# bat_v.net
KiCad netlist of a schematic drawn in Altium Designer
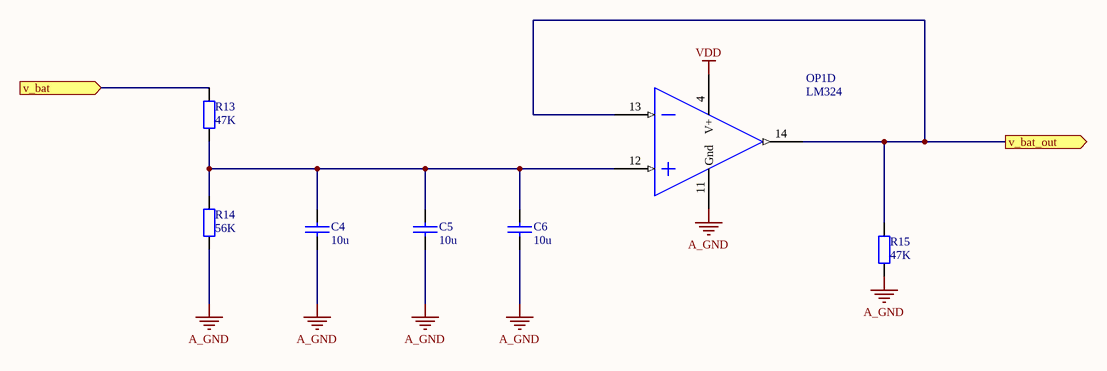
[diagram p0: bat_v.SchDoc]

(export (version "E")
  (design (tool "Eeschema 10.0.6"))
  (components
    (comp (ref "C4") (value "10u") (description "Capacitor") (libsource (lib "EceParts") (part "Cap")))
    (comp (ref "C5") (value "10u") (description "Capacitor") (libsource (lib "EceParts") (part "Cap")))
    (comp (ref "C6") (value "10u") (description "Capacitor") (libsource (lib "EceParts") (part "Cap")))
    (comp (ref "OP1") (value "LM324") (libsource (lib "EceParts") (part "LM324")))
    (comp (ref "R13") (value "47K") (description "Resistor") (libsource (lib "EceParts") (part "Resistor")))
    (comp (ref "R14") (value "56K") (description "Resistor") (libsource (lib "EceParts") (part "Resistor")))
    (comp (ref "R15") (value "47K") (description "Resistor") (libsource (lib "EceParts") (part "Resistor")))
  )
  (nets
    (net (code "1") (name "/v_bat") (class "Default")
      (node (ref "R13") (pin "2") (pinfunction "2_2") (pintype "passive"))
    )
    (net (code "2") (name "/v_bat_out") (class "Default")
      (node (ref "OP1") (pin "13") (pinfunction "IN4(-)_13") (pintype "input"))
      (node (ref "OP1") (pin "14") (pinfunction "OUT4_14") (pintype "output"))
      (node (ref "R15") (pin "2") (pinfunction "2_2") (pintype "passive"))
    )
    (net (code "3") (name "A_GND") (class "Default")
      (node (ref "C4") (pin "1") (pinfunction "1_1") (pintype "passive"))
      (node (ref "C5") (pin "1") (pinfunction "1_1") (pintype "passive"))
      (node (ref "C6") (pin "1") (pinfunction "1_1") (pintype "passive"))
      (node (ref "OP1") (pin "11") (pinfunction "Gnd_11") (pintype "power_in"))
      (node (ref "R14") (pin "1") (pinfunction "1_1") (pintype "passive"))
      (node (ref "R15") (pin "1") (pinfunction "1_1") (pintype "passive"))
    )
    (net (code "4") (name "Net-(OP1D-IN4(+))") (class "Default")
      (node (ref "C4") (pin "2") (pinfunction "2_2") (pintype "passive"))
      (node (ref "C5") (pin "2") (pinfunction "2_2") (pintype "passive"))
      (node (ref "C6") (pin "2") (pinfunction "2_2") (pintype "passive"))
      (node (ref "OP1") (pin "12") (pinfunction "IN4(+)_12") (pintype "input"))
      (node (ref "R13") (pin "1") (pinfunction "1_1") (pintype "passive"))
      (node (ref "R14") (pin "2") (pinfunction "2_2") (pintype "passive"))
    )
    (net (code "5") (name "VDD") (class "Default")
      (node (ref "OP1") (pin "4") (pinfunction "V+_4") (pintype "power_in"))
    )
  )
)
